# design1.net
KiCad netlist of a schematic drawn in Altium Designer
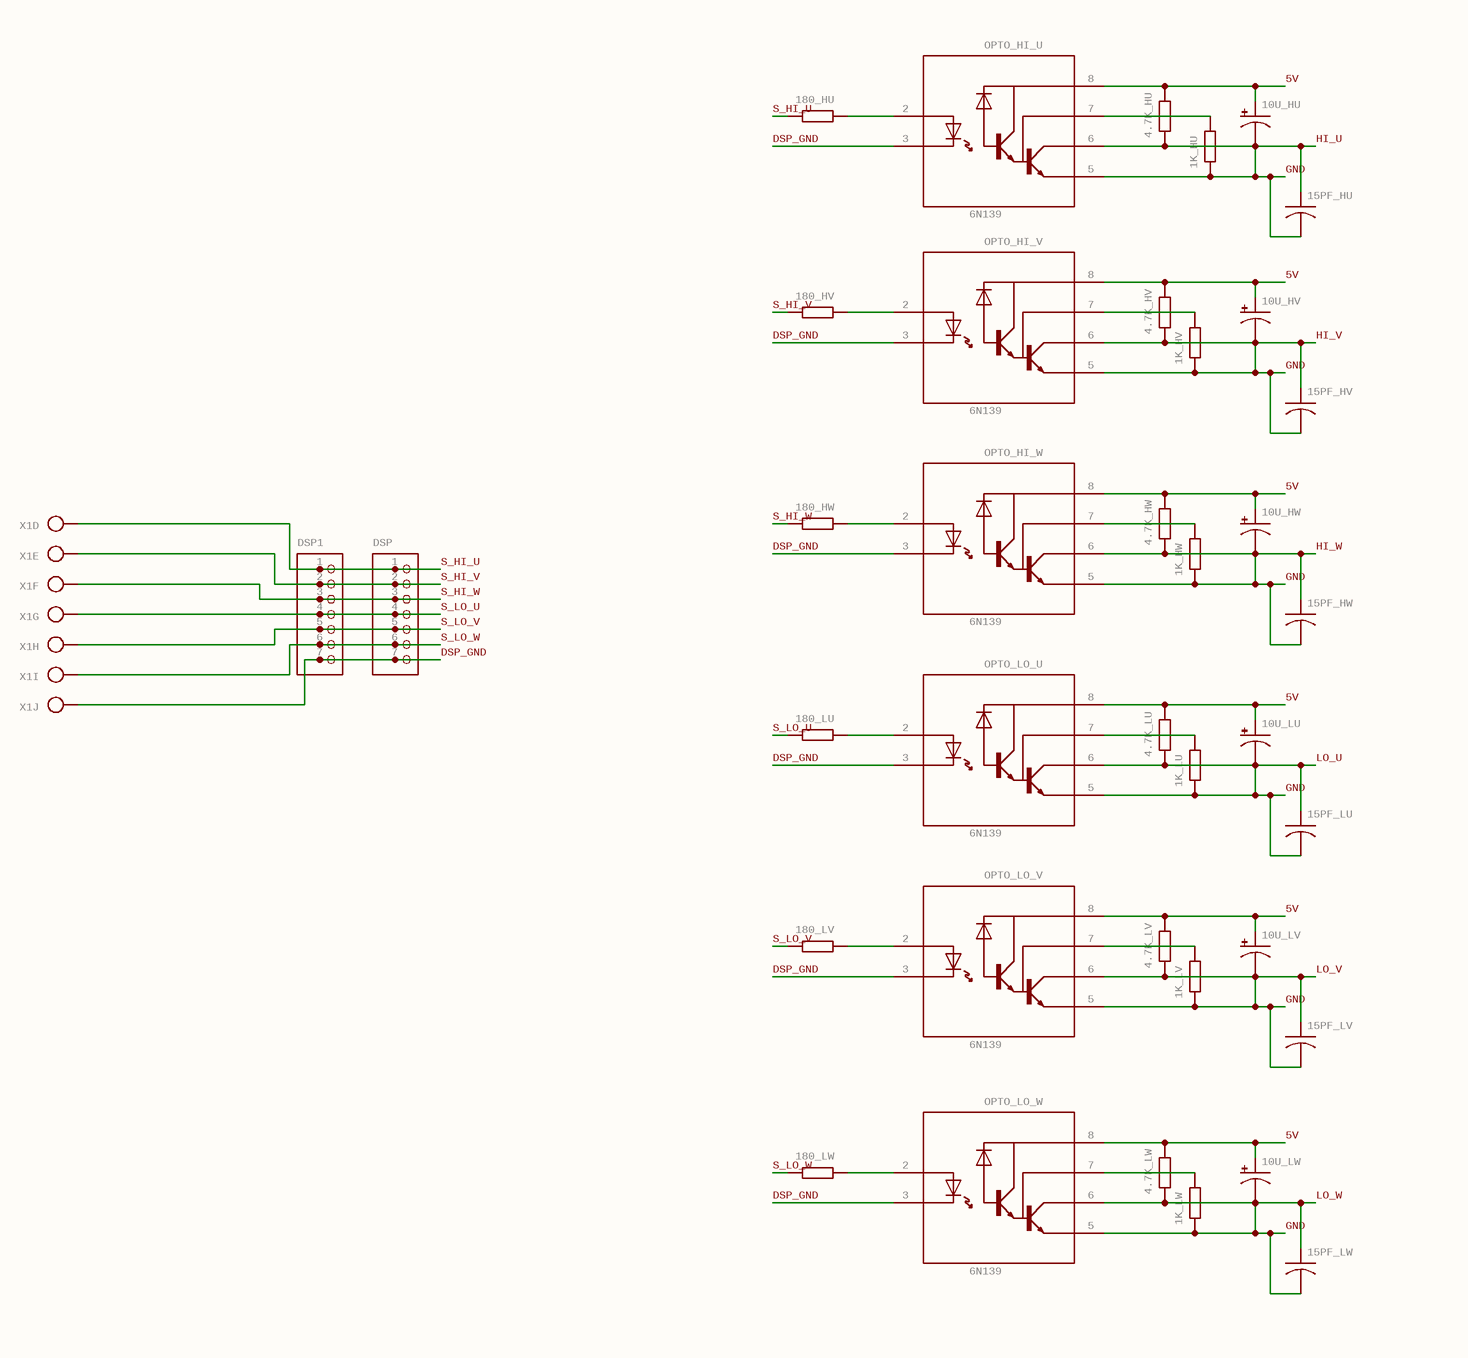
[diagram p0: design1.SchDoc, left]
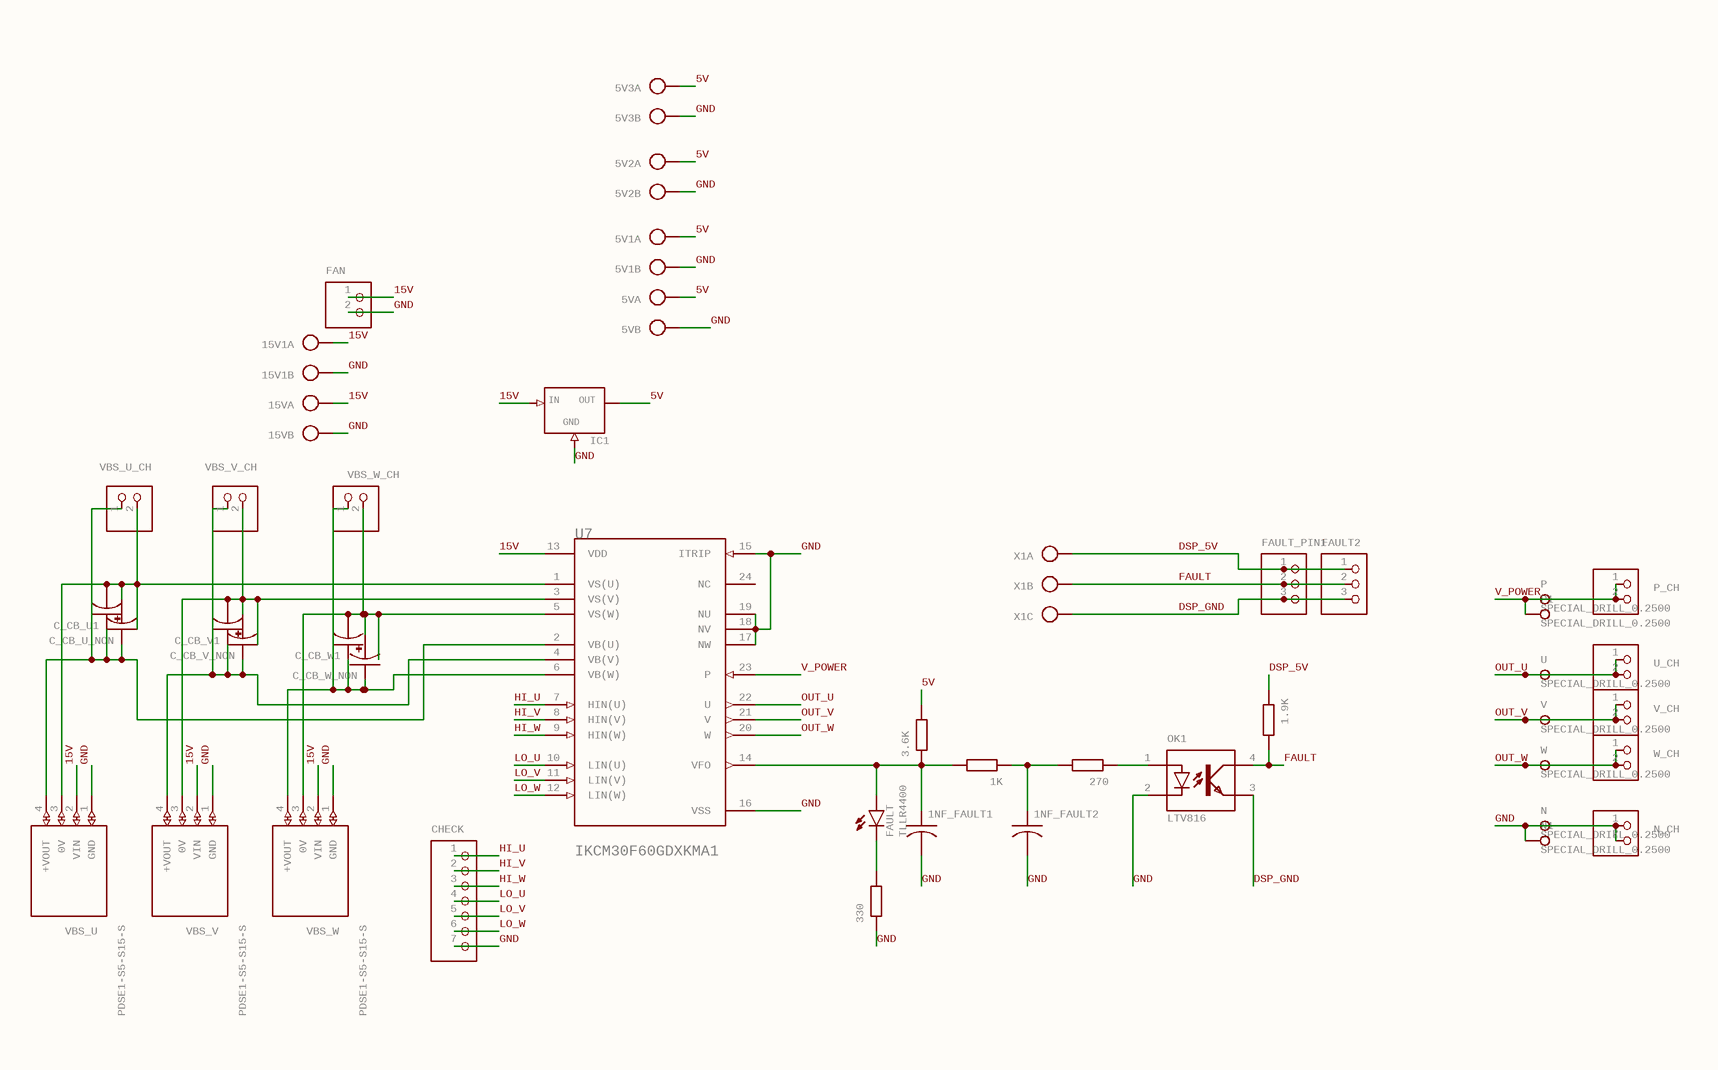
[diagram p1: design1.SchDoc, right]

(export (version "E")
  (design (tool "Eeschema 10.0.6"))
  (components
    (comp (ref "1.9K")
      (value "R-EU_0207/12")
      (footprint "0207/12")
      (description "RESISTOR, European symbol")
      (libsource (lib "rcl") (part "R-EU_0207/12"))
    )
    (comp (ref "1K")
      (value "R-EU_0207/12")
      (footprint "0207/12")
      (description "RESISTOR, European symbol")
      (libsource (lib "rcl") (part "R-EU_0207/12"))
    )
    (comp (ref "1K_HU")
      (value "R-EU_0207/12")
      (footprint "0207/12")
      (description "RESISTOR, European symbol")
      (libsource (lib "rcl") (part "R-EU_0207/12"))
    )
    (comp (ref "1K_HV")
      (value "R-EU_0207/12")
      (footprint "0207/12")
      (description "RESISTOR, European symbol")
      (libsource (lib "rcl") (part "R-EU_0207/12"))
    )
    (comp (ref "1K_HW")
      (value "R-EU_0207/12")
      (footprint "0207/12")
      (description "RESISTOR, European symbol")
      (libsource (lib "rcl") (part "R-EU_0207/12"))
    )
    (comp (ref "1K_LU")
      (value "R-EU_0207/12")
      (footprint "0207/12")
      (description "RESISTOR, European symbol")
      (libsource (lib "rcl") (part "R-EU_0207/12"))
    )
    (comp (ref "1K_LV")
      (value "R-EU_0207/12")
      (footprint "0207/12")
      (description "RESISTOR, European symbol")
      (libsource (lib "rcl") (part "R-EU_0207/12"))
    )
    (comp (ref "1K_LW")
      (value "R-EU_0207/12")
      (footprint "0207/12")
      (description "RESISTOR, European symbol")
      (libsource (lib "rcl") (part "R-EU_0207/12"))
    )
    (comp (ref "1NF_FAULT1")
      (value "C-US025-025X050")
      (footprint "C025-025X050")
      (description "CAPACITOR, American symbol")
      (libsource (lib "rcl") (part "C-US025-025X050"))
    )
    (comp (ref "1NF_FAULT2")
      (value "C-US025-025X050")
      (footprint "C025-025X050")
      (description "CAPACITOR, American symbol")
      (libsource (lib "rcl") (part "C-US025-025X050"))
    )
    (comp (ref "3.6K")
      (value "R-EU_0207/12")
      (footprint "0207/12")
      (description "RESISTOR, European symbol")
      (libsource (lib "rcl") (part "R-EU_0207/12"))
    )
    (comp (ref "4.7K_HU")
      (value "R-EU_0207/12")
      (footprint "0207/12")
      (description "RESISTOR, European symbol")
      (libsource (lib "rcl") (part "R-EU_0207/12"))
    )
    (comp (ref "4.7K_HV")
      (value "R-EU_0207/12")
      (footprint "0207/12")
      (description "RESISTOR, European symbol")
      (libsource (lib "rcl") (part "R-EU_0207/12"))
    )
    (comp (ref "4.7K_HW")
      (value "R-EU_0207/12")
      (footprint "0207/12")
      (description "RESISTOR, European symbol")
      (libsource (lib "rcl") (part "R-EU_0207/12"))
    )
    (comp (ref "4.7K_LU")
      (value "R-EU_0207/12")
      (footprint "0207/12")
      (description "RESISTOR, European symbol")
      (libsource (lib "rcl") (part "R-EU_0207/12"))
    )
    (comp (ref "4.7K_LV")
      (value "R-EU_0207/12")
      (footprint "0207/12")
      (description "RESISTOR, European symbol")
      (libsource (lib "rcl") (part "R-EU_0207/12"))
    )
    (comp (ref "4.7K_LW")
      (value "R-EU_0207/12")
      (footprint "0207/12")
      (description "RESISTOR, European symbol")
      (libsource (lib "rcl") (part "R-EU_0207/12"))
    )
    (comp (ref "5V")
      (value "AK500/2")
      (footprint "AK500/2")
      (description "CONNECTOR")
      (fields (field (name "MF") "MF") (field (name "MPN") "MPN") (field (name "LIBRARYNAME") "con-ptr500"))
      (libsource (lib "con-ptr500") (part "AK500/2"))
    )
    (comp (ref "5V1")
      (value "AK500/2")
      (footprint "AK500/2")
      (description "CONNECTOR")
      (fields (field (name "MF") "MF") (field (name "MPN") "MPN") (field (name "LIBRARYNAME") "con-ptr500"))
      (libsource (lib "con-ptr500") (part "AK500/2"))
    )
    (comp (ref "5V2")
      (value "AK500/2")
      (footprint "AK500/2")
      (description "CONNECTOR")
      (fields (field (name "MF") "MF") (field (name "MPN") "MPN") (field (name "LIBRARYNAME") "con-ptr500"))
      (libsource (lib "con-ptr500") (part "AK500/2"))
    )
    (comp (ref "5V3")
      (value "AK500/2")
      (footprint "AK500/2")
      (description "CONNECTOR")
      (fields (field (name "MF") "MF") (field (name "MPN") "MPN") (field (name "LIBRARYNAME") "con-ptr500"))
      (libsource (lib "con-ptr500") (part "AK500/2"))
    )
    (comp (ref "10U_HU")
      (value "CPOL-USE2-4")
      (footprint "E2-4")
      (description "POLARIZED CAPACITOR, American symbol")
      (libsource (lib "rcl") (part "CPOL-USE2-4"))
    )
    (comp (ref "10U_HV")
      (value "CPOL-USE2-4")
      (footprint "E2-4")
      (description "POLARIZED CAPACITOR, American symbol")
      (libsource (lib "rcl") (part "CPOL-USE2-4"))
    )
    (comp (ref "10U_HW")
      (value "CPOL-USE2-4")
      (footprint "E2-4")
      (description "POLARIZED CAPACITOR, American symbol")
      (libsource (lib "rcl") (part "CPOL-USE2-4"))
    )
    (comp (ref "10U_LU")
      (value "CPOL-USE2-4")
      (footprint "E2-4")
      (description "POLARIZED CAPACITOR, American symbol")
      (libsource (lib "rcl") (part "CPOL-USE2-4"))
    )
    (comp (ref "10U_LV")
      (value "CPOL-USE2-4")
      (footprint "E2-4")
      (description "POLARIZED CAPACITOR, American symbol")
      (libsource (lib "rcl") (part "CPOL-USE2-4"))
    )
    (comp (ref "10U_LW")
      (value "CPOL-USE2-4")
      (footprint "E2-4")
      (description "POLARIZED CAPACITOR, American symbol")
      (libsource (lib "rcl") (part "CPOL-USE2-4"))
    )
    (comp (ref "15PF_HU")
      (value "C-US025-025X050")
      (footprint "C025-025X050")
      (description "CAPACITOR, American symbol")
      (libsource (lib "rcl") (part "C-US025-025X050"))
    )
    (comp (ref "15PF_HV")
      (value "C-US025-025X050")
      (footprint "C025-025X050")
      (description "CAPACITOR, American symbol")
      (libsource (lib "rcl") (part "C-US025-025X050"))
    )
    (comp (ref "15PF_HW")
      (value "C-US025-025X050")
      (footprint "C025-025X050")
      (description "CAPACITOR, American symbol")
      (libsource (lib "rcl") (part "C-US025-025X050"))
    )
    (comp (ref "15PF_LU")
      (value "C-US025-025X050")
      (footprint "C025-025X050")
      (description "CAPACITOR, American symbol")
      (libsource (lib "rcl") (part "C-US025-025X050"))
    )
    (comp (ref "15PF_LV")
      (value "C-US025-025X050")
      (footprint "C025-025X050")
      (description "CAPACITOR, American symbol")
      (libsource (lib "rcl") (part "C-US025-025X050"))
    )
    (comp (ref "15PF_LW")
      (value "C-US025-025X050")
      (footprint "C025-025X050")
      (description "CAPACITOR, American symbol")
      (libsource (lib "rcl") (part "C-US025-025X050"))
    )
    (comp (ref "15V")
      (value "AK500/2")
      (footprint "AK500/2")
      (description "CONNECTOR")
      (fields (field (name "MF") "MF") (field (name "MPN") "MPN") (field (name "LIBRARYNAME") "con-ptr500"))
      (libsource (lib "con-ptr500") (part "AK500/2"))
    )
    (comp (ref "15V1")
      (value "AK500/2")
      (footprint "AK500/2")
      (description "CONNECTOR")
      (fields (field (name "MF") "MF") (field (name "MPN") "MPN") (field (name "LIBRARYNAME") "con-ptr500"))
      (libsource (lib "con-ptr500") (part "AK500/2"))
    )
    (comp (ref "180_HU")
      (value "R-EU_0207/12")
      (footprint "0207/12")
      (description "RESISTOR, European symbol")
      (libsource (lib "rcl") (part "R-EU_0207/12"))
    )
    (comp (ref "180_HV")
      (value "R-EU_0207/12")
      (footprint "0207/12")
      (description "RESISTOR, European symbol")
      (libsource (lib "rcl") (part "R-EU_0207/12"))
    )
    (comp (ref "180_HW")
      (value "R-EU_0207/12")
      (footprint "0207/12")
      (description "RESISTOR, European symbol")
      (libsource (lib "rcl") (part "R-EU_0207/12"))
    )
    (comp (ref "180_LU")
      (value "R-EU_0207/12")
      (footprint "0207/12")
      (description "RESISTOR, European symbol")
      (libsource (lib "rcl") (part "R-EU_0207/12"))
    )
    (comp (ref "180_LV")
      (value "R-EU_0207/12")
      (footprint "0207/12")
      (description "RESISTOR, European symbol")
      (libsource (lib "rcl") (part "R-EU_0207/12"))
    )
    (comp (ref "180_LW")
      (value "R-EU_0207/12")
      (footprint "0207/12")
      (description "RESISTOR, European symbol")
      (libsource (lib "rcl") (part "R-EU_0207/12"))
    )
    (comp (ref "270")
      (value "R-EU_0207/12")
      (footprint "0207/12")
      (description "RESISTOR, European symbol")
      (libsource (lib "rcl") (part "R-EU_0207/12"))
    )
    (comp (ref "330")
      (value "R-EU_0207/12")
      (footprint "0207/12")
      (description "RESISTOR, European symbol")
      (libsource (lib "rcl") (part "R-EU_0207/12"))
    )
    (comp (ref "CHECK")
      (value "PINHD-1X7")
      (footprint "1X07")
      (description "PIN HEADER")
      (fields (field (name "LIBRARYNAME") "pinhead"))
      (libsource (lib "pinhead") (part "PINHD-1X7"))
    )
    (comp (ref "C_CB_U1")
      (value "CPOL-USE2-4")
      (footprint "E2-4")
      (description "POLARIZED CAPACITOR, American symbol")
      (libsource (lib "") (part "CPOL-USE2-4_1"))
    )
    (comp (ref "C_CB_U_NON")
      (value "C-US025-025X050")
      (footprint "C025-025X050")
      (description "CAPACITOR, American symbol")
      (libsource (lib "rcl") (part "C-US025-025X050"))
    )
    (comp (ref "C_CB_V1")
      (value "CPOL-USE2-4")
      (footprint "E2-4")
      (description "POLARIZED CAPACITOR, American symbol")
      (libsource (lib "") (part "CPOL-USE2-4_1"))
    )
    (comp (ref "C_CB_V_NON")
      (value "C-US025-025X050")
      (footprint "C025-025X050")
      (description "CAPACITOR, American symbol")
      (libsource (lib "rcl") (part "C-US025-025X050"))
    )
    (comp (ref "C_CB_W1")
      (value "CPOL-USE2-4")
      (footprint "E2-4")
      (description "POLARIZED CAPACITOR, American symbol")
      (libsource (lib "") (part "CPOL-USE2-4_1"))
    )
    (comp (ref "C_CB_W_NON")
      (value "C-US025-025X050")
      (footprint "C025-025X050")
      (description "CAPACITOR, American symbol")
      (libsource (lib "rcl") (part "C-US025-025X050"))
    )
    (comp (ref "DSP")
      (value "PINHD-1X7/90")
      (footprint "1X07/90")
      (description "PIN HEADER")
      (fields (field (name "LIBRARYNAME") "pinhead"))
      (libsource (lib "pinhead") (part "PINHD-1X7/90"))
    )
    (comp (ref "DSP1")
      (value "PINHD-1X7")
      (footprint "1X07")
      (description "PIN HEADER")
      (fields (field (name "LIBRARYNAME") "pinhead"))
      (libsource (lib "pinhead") (part "PINHD-1X7"))
    )
    (comp (ref "FAN")
      (value "PINHD-1X2")
      (footprint "1X02")
      (description "PIN HEADER")
      (fields (field (name "LIBRARYNAME") "pinhead"))
      (libsource (lib "pinhead") (part "PINHD-1X2"))
    )
    (comp (ref "FAULT")
      (value "TLLR4400")
      (footprint "LED3MM")
      (description "Low Current (2mA) LED 3 mm Tinted Diffused Package color RED   Source:  Data sheet")
      (fields (field (name "MF") "VISHAY SEMICONDUCTOR"))
      (libsource (lib "led") (part "TLLR4400"))
    )
    (comp (ref "FAULT2")
      (value "PINHD-1X3/90")
      (footprint "1X03/90")
      (description "PIN HEADER")
      (fields (field (name "LIBRARYNAME") "pinhead"))
      (libsource (lib "pinhead") (part "PINHD-1X3/90"))
    )
    (comp (ref "FAULT_PIN1")
      (value "PINHD-1X3")
      (footprint "1X03")
      (description "PIN HEADER")
      (fields (field (name "LIBRARYNAME") "pinhead"))
      (libsource (lib "pinhead") (part "PINHD-1X3"))
    )
    (comp (ref "IC1")
      (value "78XXS")
      (footprint "78XXS")
      (description "VOLTAGE REGULATOR")
      (fields (field (name "GND") "GND") (field (name "IN") "IN") (field (name "OUT") "OUT"))
      (libsource (lib "v-reg") (part "78XXS"))
    )
    (comp (ref "N")
      (value "SPECIAL_DRILL_0.2500")
      (footprint "PAD_0.2500")
      (description "Special drills")
      (libsource (lib "special-drill") (part "SPECIAL_DRILL_0.2500"))
    )
    (comp (ref "N1")
      (value "SPECIAL_DRILL_0.2500")
      (footprint "PAD_0.2500")
      (description "Special drills")
      (libsource (lib "special-drill") (part "SPECIAL_DRILL_0.2500"))
    )
    (comp (ref "N_CH")
      (value "PINHD-1X2")
      (footprint "1X02")
      (description "PIN HEADER")
      (fields (field (name "LIBRARYNAME") "pinhead"))
      (libsource (lib "pinhead") (part "PINHD-1X2"))
    )
    (comp (ref "OK1")
      (value "LTV816")
      (footprint "DIL04")
      (description "OPTO COUPLER   Source: LITEON, LTV816.pdf")
      (fields (field (name "MF") "MF") (field (name "MPN") "MPN"))
      (libsource (lib "optocoupler") (part "LTV816"))
    )
    (comp (ref "OPTO_HI_U")
      (value "6N139")
      (footprint "DIP762W50P254L977H451Q8")
      (fields (field (name "MF") "Vishay Semiconductor"))
      (libsource (lib "6N139") (part "6N139"))
    )
    (comp (ref "OPTO_HI_V")
      (value "6N139")
      (footprint "DIP762W50P254L977H451Q8")
      (fields (field (name "MF") "Vishay Semiconductor"))
      (libsource (lib "6N139") (part "6N139"))
    )
    (comp (ref "OPTO_HI_W")
      (value "6N139")
      (footprint "DIP762W50P254L977H451Q8")
      (fields (field (name "MF") "Vishay Semiconductor"))
      (libsource (lib "6N139") (part "6N139"))
    )
    (comp (ref "OPTO_LO_U")
      (value "6N139")
      (footprint "DIP762W50P254L977H451Q8")
      (fields (field (name "MF") "Vishay Semiconductor"))
      (libsource (lib "6N139") (part "6N139"))
    )
    (comp (ref "OPTO_LO_V")
      (value "6N139")
      (footprint "DIP762W50P254L977H451Q8")
      (fields (field (name "MF") "Vishay Semiconductor"))
      (libsource (lib "6N139") (part "6N139"))
    )
    (comp (ref "OPTO_LO_W")
      (value "6N139")
      (footprint "DIP762W50P254L977H451Q8")
      (fields (field (name "MF") "Vishay Semiconductor"))
      (libsource (lib "6N139") (part "6N139"))
    )
    (comp (ref "P")
      (value "SPECIAL_DRILL_0.2500")
      (footprint "PAD_0.2500")
      (description "Special drills")
      (libsource (lib "special-drill") (part "SPECIAL_DRILL_0.2500"))
    )
    (comp (ref "P1")
      (value "SPECIAL_DRILL_0.2500")
      (footprint "PAD_0.2500")
      (description "Special drills")
      (libsource (lib "special-drill") (part "SPECIAL_DRILL_0.2500"))
    )
    (comp (ref "P_CH")
      (value "PINHD-1X2")
      (footprint "1X02")
      (description "PIN HEADER")
      (fields (field (name "LIBRARYNAME") "pinhead"))
      (libsource (lib "pinhead") (part "PINHD-1X2"))
    )
    (comp (ref "U")
      (value "SPECIAL_DRILL_0.2500")
      (footprint "PAD_0.2500")
      (description "Special drills")
      (libsource (lib "special-drill") (part "SPECIAL_DRILL_0.2500"))
    )
    (comp (ref "U7")
      (value "INFINEON_IKCM30F60GDXKMA1INFINEON_IKCM30F60GDXKMA1_0_0")
      (footprint "INFINEON_IKCM30F60GDXKMA1_0")
      (description "Trans IGBT Module N-CH 24-Pin MDIP")
      (fields
        (field (name "IKCM30F60GDXKMA1") "IKCM30F60GDXKMA1")
        (field (name "DIGIKEY_PART_NUMBER") "IKCM30F60GDXKMA1-ND")
        (field (name "MF") "Infineon")
      )
      (libsource (lib "Infineon - IKCM30F60GDXKMA1") (part "INFINEON_IKCM30F60GDXKMA1INFINEON_IKCM30F60GDXKMA1_0_0"))
    )
    (comp (ref "U_CH")
      (value "PINHD-1X2")
      (footprint "1X02")
      (description "PIN HEADER")
      (fields (field (name "LIBRARYNAME") "pinhead"))
      (libsource (lib "pinhead") (part "PINHD-1X2"))
    )
    (comp (ref "V")
      (value "SPECIAL_DRILL_0.2500")
      (footprint "PAD_0.2500")
      (description "Special drills")
      (libsource (lib "special-drill") (part "SPECIAL_DRILL_0.2500"))
    )
    (comp (ref "VBS_U")
      (value "PDSE1-S5-S15-S")
      (footprint "PDSE1S5S15S")
      (fields (field (name "UTMEL_PART_NUMBER") "UTMEL_PART_NUMBER"))
      (libsource (lib "PDSE1-S5-S15-S") (part "PDSE1-S5-S15-S"))
    )
    (comp (ref "VBS_U_CH")
      (value "PINHD-1X2")
      (footprint "1X02")
      (description "PIN HEADER")
      (fields (field (name "LIBRARYNAME") "pinhead"))
      (libsource (lib "pinhead") (part "PINHD-1X2"))
    )
    (comp (ref "VBS_V")
      (value "PDSE1-S5-S15-S")
      (footprint "PDSE1S5S15S")
      (fields (field (name "UTMEL_PART_NUMBER") "UTMEL_PART_NUMBER"))
      (libsource (lib "PDSE1-S5-S15-S") (part "PDSE1-S5-S15-S"))
    )
    (comp (ref "VBS_V_CH")
      (value "PINHD-1X2")
      (footprint "1X02")
      (description "PIN HEADER")
      (fields (field (name "LIBRARYNAME") "pinhead"))
      (libsource (lib "pinhead") (part "PINHD-1X2"))
    )
    (comp (ref "VBS_W")
      (value "PDSE1-S5-S15-S")
      (footprint "PDSE1S5S15S")
      (fields (field (name "UTMEL_PART_NUMBER") "UTMEL_PART_NUMBER"))
      (libsource (lib "PDSE1-S5-S15-S") (part "PDSE1-S5-S15-S"))
    )
    (comp (ref "VBS_W_CH")
      (value "PINHD-1X2")
      (footprint "1X02")
      (description "PIN HEADER")
      (fields (field (name "LIBRARYNAME") "pinhead"))
      (libsource (lib "pinhead") (part "PINHD-1X2"))
    )
    (comp (ref "V_CH")
      (value "PINHD-1X2")
      (footprint "1X02")
      (description "PIN HEADER")
      (fields (field (name "LIBRARYNAME") "pinhead"))
      (libsource (lib "pinhead") (part "PINHD-1X2"))
    )
    (comp (ref "W")
      (value "SPECIAL_DRILL_0.2500")
      (footprint "PAD_0.2500")
      (description "Special drills")
      (libsource (lib "special-drill") (part "SPECIAL_DRILL_0.2500"))
    )
    (comp (ref "W_CH")
      (value "PINHD-1X2")
      (footprint "1X02")
      (description "PIN HEADER")
      (fields (field (name "LIBRARYNAME") "pinhead"))
      (libsource (lib "pinhead") (part "PINHD-1X2"))
    )
    (comp (ref "X1")
      (value "AK500/10")
      (footprint "AK500/10")
      (description "CONNECTOR")
      (fields (field (name "MF") "MF") (field (name "MPN") "MPN") (field (name "LIBRARYNAME") "con-ptr500"))
      (libsource (lib "con-ptr500") (part "AK500/10"))
    )
  )
  (nets
    (net (code "1") (name "/5V") (class "Default")
      (node (ref "10U_HU") (pin "+") (pinfunction "+_+") (pintype "passive"))
      (node (ref "10U_HV") (pin "+") (pinfunction "+_+") (pintype "passive"))
      (node (ref "10U_HW") (pin "+") (pinfunction "+_+") (pintype "passive"))
      (node (ref "10U_LU") (pin "+") (pinfunction "+_+") (pintype "passive"))
      (node (ref "10U_LV") (pin "+") (pinfunction "+_+") (pintype "passive"))
      (node (ref "10U_LW") (pin "+") (pinfunction "+_+") (pintype "passive"))
      (node (ref "3.6K") (pin "2") (pinfunction "2_2") (pintype "passive"))
      (node (ref "4.7K_HU") (pin "2") (pinfunction "2_2") (pintype "passive"))
      (node (ref "4.7K_HV") (pin "2") (pinfunction "2_2") (pintype "passive"))
      (node (ref "4.7K_HW") (pin "2") (pinfunction "2_2") (pintype "passive"))
      (node (ref "4.7K_LU") (pin "2") (pinfunction "2_2") (pintype "passive"))
      (node (ref "4.7K_LV") (pin "2") (pinfunction "2_2") (pintype "passive"))
      (node (ref "4.7K_LW") (pin "2") (pinfunction "2_2") (pintype "passive"))
      (node (ref "5V") (pin "1") (pinfunction "KL_1") (pintype "passive"))
      (node (ref "5V1") (pin "1") (pinfunction "KL_1") (pintype "passive"))
      (node (ref "5V2") (pin "1") (pinfunction "KL_1") (pintype "passive"))
      (node (ref "5V3") (pin "1") (pinfunction "KL_1") (pintype "passive"))
      (node (ref "IC1") (pin "OUT") (pinfunction "OUT_OUT") (pintype "passive"))
      (node (ref "OPTO_HI_U") (pin "8") (pinfunction "VCC_8") (pintype "power_in"))
      (node (ref "OPTO_HI_V") (pin "8") (pinfunction "VCC_8") (pintype "power_in"))
      (node (ref "OPTO_HI_W") (pin "8") (pinfunction "VCC_8") (pintype "power_in"))
      (node (ref "OPTO_LO_U") (pin "8") (pinfunction "VCC_8") (pintype "power_in"))
      (node (ref "OPTO_LO_V") (pin "8") (pinfunction "VCC_8") (pintype "power_in"))
      (node (ref "OPTO_LO_W") (pin "8") (pinfunction "VCC_8") (pintype "power_in"))
    )
    (net (code "2") (name "/15V") (class "Default")
      (node (ref "15V") (pin "1") (pinfunction "KL_1") (pintype "passive"))
      (node (ref "15V1") (pin "1") (pinfunction "KL_1") (pintype "passive"))
      (node (ref "FAN") (pin "1") (pinfunction "1_1") (pintype "passive"))
      (node (ref "IC1") (pin "IN") (pinfunction "IN_IN") (pintype "input"))
      (node (ref "U7") (pin "13") (pinfunction "VDD_13") (pintype "power_in"))
      (node (ref "VBS_U") (pin "2") (pinfunction "VIN_2") (pintype "bidirectional"))
      (node (ref "VBS_V") (pin "2") (pinfunction "VIN_2") (pintype "bidirectional"))
      (node (ref "VBS_W") (pin "2") (pinfunction "VIN_2") (pintype "bidirectional"))
    )
    (net (code "3") (name "/DSP_5V") (class "Default")
      (node (ref "1.9K") (pin "1") (pinfunction "1_1") (pintype "passive"))
      (node (ref "FAULT2") (pin "1") (pinfunction "1_1") (pintype "passive"))
      (node (ref "FAULT_PIN1") (pin "1") (pinfunction "1_1") (pintype "passive"))
      (node (ref "X1") (pin "1") (pinfunction "KL_1") (pintype "passive"))
    )
    (net (code "4") (name "/DSP_GND") (class "Default")
      (node (ref "DSP") (pin "7") (pinfunction "7_7") (pintype "passive"))
      (node (ref "DSP1") (pin "7") (pinfunction "7_7") (pintype "passive"))
      (node (ref "FAULT2") (pin "3") (pinfunction "3_3") (pintype "passive"))
      (node (ref "FAULT_PIN1") (pin "3") (pinfunction "3_3") (pintype "passive"))
      (node (ref "OK1") (pin "3") (pinfunction "EMIT_3") (pintype "passive"))
      (node (ref "OPTO_HI_U") (pin "3") (pinfunction "C_3") (pintype "passive"))
      (node (ref "OPTO_HI_V") (pin "3") (pinfunction "C_3") (pintype "passive"))
      (node (ref "OPTO_HI_W") (pin "3") (pinfunction "C_3") (pintype "passive"))
      (node (ref "OPTO_LO_U") (pin "3") (pinfunction "C_3") (pintype "passive"))
      (node (ref "OPTO_LO_V") (pin "3") (pinfunction "C_3") (pintype "passive"))
      (node (ref "OPTO_LO_W") (pin "3") (pinfunction "C_3") (pintype "passive"))
      (node (ref "X1") (pin "10") (pinfunction "KL_10") (pintype "passive"))
      (node (ref "X1") (pin "3") (pinfunction "KL_3") (pintype "passive"))
    )
    (net (code "5") (name "/FAULT") (class "Default")
      (node (ref "1.9K") (pin "2") (pinfunction "2_2") (pintype "passive"))
      (node (ref "FAULT2") (pin "2") (pinfunction "2_2") (pintype "passive"))
      (node (ref "FAULT_PIN1") (pin "2") (pinfunction "2_2") (pintype "passive"))
      (node (ref "OK1") (pin "4") (pinfunction "COL_4") (pintype "passive"))
      (node (ref "X1") (pin "2") (pinfunction "KL_2") (pintype "passive"))
    )
    (net (code "6") (name "/GND") (class "Default")
      (node (ref "10U_HU") (pin "-") (pinfunction "-_-") (pintype "passive"))
      (node (ref "10U_HV") (pin "-") (pinfunction "-_-") (pintype "passive"))
      (node (ref "10U_HW") (pin "-") (pinfunction "-_-") (pintype "passive"))
      (node (ref "10U_LU") (pin "-") (pinfunction "-_-") (pintype "passive"))
      (node (ref "10U_LV") (pin "-") (pinfunction "-_-") (pintype "passive"))
      (node (ref "10U_LW") (pin "-") (pinfunction "-_-") (pintype "passive"))
      (node (ref "15PF_HU") (pin "1") (pinfunction "1_1") (pintype "passive"))
      (node (ref "15PF_HU") (pin "2") (pinfunction "2_2") (pintype "passive"))
      (node (ref "15PF_HV") (pin "1") (pinfunction "1_1") (pintype "passive"))
      (node (ref "15PF_HV") (pin "2") (pinfunction "2_2") (pintype "passive"))
      (node (ref "15PF_HW") (pin "1") (pinfunction "1_1") (pintype "passive"))
      (node (ref "15PF_HW") (pin "2") (pinfunction "2_2") (pintype "passive"))
      (node (ref "15PF_LU") (pin "1") (pinfunction "1_1") (pintype "passive"))
      (node (ref "15PF_LU") (pin "2") (pinfunction "2_2") (pintype "passive"))
      (node (ref "15PF_LV") (pin "1") (pinfunction "1_1") (pintype "passive"))
      (node (ref "15PF_LV") (pin "2") (pinfunction "2_2") (pintype "passive"))
      (node (ref "15PF_LW") (pin "1") (pinfunction "1_1") (pintype "passive"))
      (node (ref "15PF_LW") (pin "2") (pinfunction "2_2") (pintype "passive"))
      (node (ref "15V") (pin "2") (pinfunction "KL_2") (pintype "passive"))
      (node (ref "15V1") (pin "2") (pinfunction "KL_2") (pintype "passive"))
      (node (ref "1K_HU") (pin "1") (pinfunction "1_1") (pintype "passive"))
      (node (ref "1K_HV") (pin "1") (pinfunction "1_1") (pintype "passive"))
      (node (ref "1K_HW") (pin "1") (pinfunction "1_1") (pintype "passive"))
      (node (ref "1K_LU") (pin "1") (pinfunction "1_1") (pintype "passive"))
      (node (ref "1K_LV") (pin "1") (pinfunction "1_1") (pintype "passive"))
      (node (ref "1K_LW") (pin "1") (pinfunction "1_1") (pintype "passive"))
      (node (ref "1NF_FAULT1") (pin "2") (pinfunction "2_2") (pintype "passive"))
      (node (ref "1NF_FAULT2") (pin "2") (pinfunction "2_2") (pintype "passive"))
      (node (ref "330") (pin "1") (pinfunction "1_1") (pintype "passive"))
      (node (ref "4.7K_HU") (pin "1") (pinfunction "1_1") (pintype "passive"))
      (node (ref "4.7K_HV") (pin "1") (pinfunction "1_1") (pintype "passive"))
      (node (ref "4.7K_HW") (pin "1") (pinfunction "1_1") (pintype "passive"))
      (node (ref "4.7K_LU") (pin "1") (pinfunction "1_1") (pintype "passive"))
      (node (ref "4.7K_LV") (pin "1") (pinfunction "1_1") (pintype "passive"))
      (node (ref "4.7K_LW") (pin "1") (pinfunction "1_1") (pintype "passive"))
      (node (ref "5V") (pin "2") (pinfunction "KL_2") (pintype "passive"))
      (node (ref "5V1") (pin "2") (pinfunction "KL_2") (pintype "passive"))
      (node (ref "5V2") (pin "2") (pinfunction "KL_2") (pintype "passive"))
      (node (ref "5V3") (pin "2") (pinfunction "KL_2") (pintype "passive"))
      (node (ref "CHECK") (pin "1") (pinfunction "1_1") (pintype "passive"))
      (node (ref "CHECK") (pin "2") (pinfunction "2_2") (pintype "passive"))
      (node (ref "CHECK") (pin "3") (pinfunction "3_3") (pintype "passive"))
      (node (ref "CHECK") (pin "4") (pinfunction "4_4") (pintype "passive"))
      (node (ref "CHECK") (pin "5") (pinfunction "5_5") (pintype "passive"))
      (node (ref "CHECK") (pin "6") (pinfunction "6_6") (pintype "passive"))
      (node (ref "CHECK") (pin "7") (pinfunction "7_7") (pintype "passive"))
      (node (ref "FAN") (pin "2") (pinfunction "2_2") (pintype "passive"))
      (node (ref "IC1") (pin "GND") (pinfunction "GND_GND") (pintype "input"))
      (node (ref "N") (pin "1") (pinfunction "1_1") (pintype "passive"))
      (node (ref "N1") (pin "1") (pinfunction "1_1") (pintype "passive"))
      (node (ref "N_CH") (pin "1") (pinfunction "1_1") (pintype "passive"))
      (node (ref "N_CH") (pin "2") (pinfunction "2_2") (pintype "passive"))
      (node (ref "OK1") (pin "2") (pinfunction "C_2") (pintype "passive"))
      (node (ref "OPTO_HI_U") (pin "5") (pinfunction "GND_5") (pintype "power_in"))
      (node (ref "OPTO_HI_U") (pin "6") (pinfunction "VO_6") (pintype "passive"))
      (node (ref "OPTO_HI_V") (pin "5") (pinfunction "GND_5") (pintype "power_in"))
      (node (ref "OPTO_HI_V") (pin "6") (pinfunction "VO_6") (pintype "passive"))
      (node (ref "OPTO_HI_W") (pin "5") (pinfunction "GND_5") (pintype "power_in"))
      (node (ref "OPTO_HI_W") (pin "6") (pinfunction "VO_6") (pintype "passive"))
      (node (ref "OPTO_LO_U") (pin "5") (pinfunction "GND_5") (pintype "power_in"))
      (node (ref "OPTO_LO_U") (pin "6") (pinfunction "VO_6") (pintype "passive"))
      (node (ref "OPTO_LO_V") (pin "5") (pinfunction "GND_5") (pintype "power_in"))
      (node (ref "OPTO_LO_V") (pin "6") (pinfunction "VO_6") (pintype "passive"))
      (node (ref "OPTO_LO_W") (pin "5") (pinfunction "GND_5") (pintype "power_in"))
      (node (ref "OPTO_LO_W") (pin "6") (pinfunction "VO_6") (pintype "passive"))
      (node (ref "U7") (pin "10") (pinfunction "LIN(U)_10") (pintype "input"))
      (node (ref "U7") (pin "11") (pinfunction "LIN(V)_11") (pintype "input"))
      (node (ref "U7") (pin "12") (pinfunction "LIN(W)_12") (pintype "input"))
      (node (ref "U7") (pin "15") (pinfunction "ITRIP_15") (pintype "input"))
      (node (ref "U7") (pin "16") (pinfunction "VSS_16") (pintype "power_in"))
      (node (ref "U7") (pin "17") (pinfunction "NW_17") (pintype "passive"))
      (node (ref "U7") (pin "18") (pinfunction "NV_18") (pintype "passive"))
      (node (ref "U7") (pin "19") (pinfunction "NU_19") (pintype "passive"))
      (node (ref "U7") (pin "7") (pinfunction "HIN(U)_7") (pintype "input"))
      (node (ref "U7") (pin "8") (pinfunction "HIN(V)_8") (pintype "input"))
      (node (ref "U7") (pin "9") (pinfunction "HIN(W)_9") (pintype "input"))
      (node (ref "VBS_U") (pin "1") (pinfunction "GND_1") (pintype "bidirectional"))
      (node (ref "VBS_V") (pin "1") (pinfunction "GND_1") (pintype "bidirectional"))
      (node (ref "VBS_W") (pin "1") (pinfunction "GND_1") (pintype "bidirectional"))
    )
    (net (code "7") (name "/OUT_U") (class "Default")
      (node (ref "U") (pin "1") (pinfunction "1_1") (pintype "passive"))
      (node (ref "U7") (pin "22") (pinfunction "U_22") (pintype "output"))
      (node (ref "U_CH") (pin "1") (pinfunction "1_1") (pintype "passive"))
      (node (ref "U_CH") (pin "2") (pinfunction "2_2") (pintype "passive"))
    )
    (net (code "8") (name "/OUT_V") (class "Default")
      (node (ref "U7") (pin "21") (pinfunction "V_21") (pintype "output"))
      (node (ref "V") (pin "1") (pinfunction "1_1") (pintype "passive"))
      (node (ref "V_CH") (pin "1") (pinfunction "1_1") (pintype "passive"))
      (node (ref "V_CH") (pin "2") (pinfunction "2_2") (pintype "passive"))
    )
    (net (code "9") (name "/OUT_W") (class "Default")
      (node (ref "U7") (pin "20") (pinfunction "W_20") (pintype "output"))
      (node (ref "W") (pin "1") (pinfunction "1_1") (pintype "passive"))
      (node (ref "W_CH") (pin "1") (pinfunction "1_1") (pintype "passive"))
      (node (ref "W_CH") (pin "2") (pinfunction "2_2") (pintype "passive"))
    )
    (net (code "10") (name "/S_HI_U") (class "Default")
      (node (ref "180_HU") (pin "1") (pinfunction "1_1") (pintype "passive"))
      (node (ref "DSP") (pin "1") (pinfunction "1_1") (pintype "passive"))
      (node (ref "DSP1") (pin "1") (pinfunction "1_1") (pintype "passive"))
      (node (ref "X1") (pin "4") (pinfunction "KL_4") (pintype "passive"))
    )
    (net (code "11") (name "/S_HI_V") (class "Default")
      (node (ref "180_HV") (pin "1") (pinfunction "1_1") (pintype "passive"))
      (node (ref "DSP") (pin "2") (pinfunction "2_2") (pintype "passive"))
      (node (ref "DSP1") (pin "2") (pinfunction "2_2") (pintype "passive"))
      (node (ref "X1") (pin "5") (pinfunction "KL_5") (pintype "passive"))
    )
    (net (code "12") (name "/S_HI_W") (class "Default")
      (node (ref "180_HW") (pin "1") (pinfunction "1_1") (pintype "passive"))
      (node (ref "DSP") (pin "3") (pinfunction "3_3") (pintype "passive"))
      (node (ref "DSP1") (pin "3") (pinfunction "3_3") (pintype "passive"))
      (node (ref "X1") (pin "6") (pinfunction "KL_6") (pintype "passive"))
    )
    (net (code "13") (name "/S_LO_U") (class "Default")
      (node (ref "180_LU") (pin "1") (pinfunction "1_1") (pintype "passive"))
      (node (ref "DSP") (pin "4") (pinfunction "4_4") (pintype "passive"))
      (node (ref "DSP1") (pin "4") (pinfunction "4_4") (pintype "passive"))
      (node (ref "X1") (pin "7") (pinfunction "KL_7") (pintype "passive"))
    )
    (net (code "14") (name "/S_LO_V") (class "Default")
      (node (ref "180_LV") (pin "1") (pinfunction "1_1") (pintype "passive"))
      (node (ref "DSP") (pin "5") (pinfunction "5_5") (pintype "passive"))
      (node (ref "DSP1") (pin "5") (pinfunction "5_5") (pintype "passive"))
      (node (ref "X1") (pin "8") (pinfunction "KL_8") (pintype "passive"))
    )
    (net (code "15") (name "/S_LO_W") (class "Default")
      (node (ref "180_LW") (pin "1") (pinfunction "1_1") (pintype "passive"))
      (node (ref "DSP") (pin "6") (pinfunction "6_6") (pintype "passive"))
      (node (ref "DSP1") (pin "6") (pinfunction "6_6") (pintype "passive"))
      (node (ref "X1") (pin "9") (pinfunction "KL_9") (pintype "passive"))
    )
    (net (code "16") (name "/V_POWER") (class "Default")
      (node (ref "P") (pin "1") (pinfunction "1_1") (pintype "passive"))
      (node (ref "P1") (pin "1") (pinfunction "1_1") (pintype "passive"))
      (node (ref "P_CH") (pin "1") (pinfunction "1_1") (pintype "passive"))
      (node (ref "P_CH") (pin "2") (pinfunction "2_2") (pintype "passive"))
      (node (ref "U7") (pin "23") (pinfunction "P_23") (pintype "input"))
    )
    (net (code "17") (name "Net-(1K-Pad1)") (class "Default")
      (node (ref "1K") (pin "1") (pinfunction "1_1") (pintype "passive"))
      (node (ref "1NF_FAULT2") (pin "1") (pinfunction "1_1") (pintype "passive"))
      (node (ref "270") (pin "2") (pinfunction "2_2") (pintype "passive"))
    )
    (net (code "18") (name "Net-(FAULT-C)") (class "Default")
      (node (ref "330") (pin "2") (pinfunction "2_2") (pintype "passive"))
      (node (ref "FAULT") (pin "K") (pinfunction "C_K") (pintype "passive"))
    )
    (net (code "19") (name "Net-(OK1-A)") (class "Default")
      (node (ref "270") (pin "1") (pinfunction "1_1") (pintype "passive"))
      (node (ref "OK1") (pin "1") (pinfunction "A_1") (pintype "passive"))
    )
    (net (code "20") (name "Net-(OPTO_HI_U-A)") (class "Default")
      (node (ref "180_HU") (pin "2") (pinfunction "2_2") (pintype "passive"))
      (node (ref "OPTO_HI_U") (pin "2") (pinfunction "A_2") (pintype "passive"))
    )
    (net (code "21") (name "Net-(OPTO_HI_U-VB)") (class "Default")
      (node (ref "1K_HU") (pin "2") (pinfunction "2_2") (pintype "passive"))
      (node (ref "OPTO_HI_U") (pin "7") (pinfunction "VB_7") (pintype "passive"))
    )
    (net (code "22") (name "Net-(OPTO_HI_V-A)") (class "Default")
      (node (ref "180_HV") (pin "2") (pinfunction "2_2") (pintype "passive"))
      (node (ref "OPTO_HI_V") (pin "2") (pinfunction "A_2") (pintype "passive"))
    )
    (net (code "23") (name "Net-(OPTO_HI_V-VB)") (class "Default")
      (node (ref "1K_HV") (pin "2") (pinfunction "2_2") (pintype "passive"))
      (node (ref "OPTO_HI_V") (pin "7") (pinfunction "VB_7") (pintype "passive"))
    )
    (net (code "24") (name "Net-(OPTO_HI_W-A)") (class "Default")
      (node (ref "180_HW") (pin "2") (pinfunction "2_2") (pintype "passive"))
      (node (ref "OPTO_HI_W") (pin "2") (pinfunction "A_2") (pintype "passive"))
    )
    (net (code "25") (name "Net-(OPTO_HI_W-VB)") (class "Default")
      (node (ref "1K_HW") (pin "2") (pinfunction "2_2") (pintype "passive"))
      (node (ref "OPTO_HI_W") (pin "7") (pinfunction "VB_7") (pintype "passive"))
    )
    (net (code "26") (name "Net-(OPTO_LO_U-A)") (class "Default")
      (node (ref "180_LU") (pin "2") (pinfunction "2_2") (pintype "passive"))
      (node (ref "OPTO_LO_U") (pin "2") (pinfunction "A_2") (pintype "passive"))
    )
    (net (code "27") (name "Net-(OPTO_LO_U-VB)") (class "Default")
      (node (ref "1K_LU") (pin "2") (pinfunction "2_2") (pintype "passive"))
      (node (ref "OPTO_LO_U") (pin "7") (pinfunction "VB_7") (pintype "passive"))
    )
    (net (code "28") (name "Net-(OPTO_LO_V-A)") (class "Default")
      (node (ref "180_LV") (pin "2") (pinfunction "2_2") (pintype "passive"))
      (node (ref "OPTO_LO_V") (pin "2") (pinfunction "A_2") (pintype "passive"))
    )
    (net (code "29") (name "Net-(OPTO_LO_V-VB)") (class "Default")
      (node (ref "1K_LV") (pin "2") (pinfunction "2_2") (pintype "passive"))
      (node (ref "OPTO_LO_V") (pin "7") (pinfunction "VB_7") (pintype "passive"))
    )
    (net (code "30") (name "Net-(OPTO_LO_W-A)") (class "Default")
      (node (ref "180_LW") (pin "2") (pinfunction "2_2") (pintype "passive"))
      (node (ref "OPTO_LO_W") (pin "2") (pinfunction "A_2") (pintype "passive"))
    )
    (net (code "31") (name "Net-(OPTO_LO_W-VB)") (class "Default")
      (node (ref "1K_LW") (pin "2") (pinfunction "2_2") (pintype "passive"))
      (node (ref "OPTO_LO_W") (pin "7") (pinfunction "VB_7") (pintype "passive"))
    )
    (net (code "32") (name "Net-(U7-VB(U))") (class "Default")
      (node (ref "C_CB_U1") (pin "+") (pinfunction "+_+") (pintype "passive"))
      (node (ref "C_CB_U_NON") (pin "1") (pinfunction "1_1") (pintype "passive"))
      (node (ref "U7") (pin "2") (pinfunction "VB(U)_2") (pintype "power_in"))
      (node (ref "VBS_U") (pin "4") (pinfunction "+VOUT_4") (pintype "bidirectional"))
      (node (ref "VBS_U_CH") (pin "1") (pinfunction "1_1") (pintype "passive"))
    )
    (net (code "33") (name "Net-(U7-VB(V))") (class "Default")
      (node (ref "C_CB_V1") (pin "+") (pinfunction "+_+") (pintype "passive"))
      (node (ref "C_CB_V_NON") (pin "1") (pinfunction "1_1") (pintype "passive"))
      (node (ref "U7") (pin "4") (pinfunction "VB(V)_4") (pintype "power_in"))
      (node (ref "VBS_V") (pin "4") (pinfunction "+VOUT_4") (pintype "bidirectional"))
      (node (ref "VBS_V_CH") (pin "1") (pinfunction "1_1") (pintype "passive"))
    )
    (net (code "34") (name "Net-(U7-VB(W))") (class "Default")
      (node (ref "C_CB_W1") (pin "+") (pinfunction "+_+") (pintype "passive"))
      (node (ref "C_CB_W_NON") (pin "1") (pinfunction "1_1") (pintype "passive"))
      (node (ref "U7") (pin "6") (pinfunction "VB(W)_6") (pintype "power_in"))
      (node (ref "VBS_W") (pin "4") (pinfunction "+VOUT_4") (pintype "bidirectional"))
      (node (ref "VBS_W_CH") (pin "1") (pinfunction "1_1") (pintype "passive"))
    )
    (net (code "35") (name "Net-(U7-VFO)") (class "Default")
      (node (ref "1K") (pin "2") (pinfunction "2_2") (pintype "passive"))
      (node (ref "1NF_FAULT1") (pin "1") (pinfunction "1_1") (pintype "passive"))
      (node (ref "3.6K") (pin "1") (pinfunction "1_1") (pintype "passive"))
      (node (ref "FAULT") (pin "A") (pinfunction "A_A") (pintype "passive"))
      (node (ref "U7") (pin "14") (pinfunction "VFO_14") (pintype "output"))
    )
    (net (code "36") (name "Net-(U7-VS(U))") (class "Default")
      (node (ref "C_CB_U1") (pin "-") (pinfunction "-_-") (pintype "passive"))
      (node (ref "C_CB_U_NON") (pin "2") (pinfunction "2_2") (pintype "passive"))
      (node (ref "U7") (pin "1") (pinfunction "VS(U)_1") (pintype "power_in"))
      (node (ref "VBS_U") (pin "3") (pinfunction "0V_3") (pintype "bidirectional"))
      (node (ref "VBS_U_CH") (pin "2") (pinfunction "2_2") (pintype "passive"))
    )
    (net (code "37") (name "Net-(U7-VS(V))") (class "Default")
      (node (ref "C_CB_V1") (pin "-") (pinfunction "-_-") (pintype "passive"))
      (node (ref "C_CB_V_NON") (pin "2") (pinfunction "2_2") (pintype "passive"))
      (node (ref "U7") (pin "3") (pinfunction "VS(V)_3") (pintype "power_in"))
      (node (ref "VBS_V") (pin "3") (pinfunction "0V_3") (pintype "bidirectional"))
      (node (ref "VBS_V_CH") (pin "2") (pinfunction "2_2") (pintype "passive"))
    )
    (net (code "38") (name "Net-(U7-VS(W))") (class "Default")
      (node (ref "C_CB_W1") (pin "-") (pinfunction "-_-") (pintype "passive"))
      (node (ref "C_CB_W_NON") (pin "2") (pinfunction "2_2") (pintype "passive"))
      (node (ref "U7") (pin "5") (pinfunction "VS(W)_5") (pintype "power_in"))
      (node (ref "VBS_W") (pin "3") (pinfunction "0V_3") (pintype "bidirectional"))
      (node (ref "VBS_W_CH") (pin "2") (pinfunction "2_2") (pintype "passive"))
    )
    (net (code "39") (name "unconnected-(U7-NC-Pad24)") (class "Default")
      (node (ref "U7") (pin "24") (pinfunction "NC_24") (pintype "passive"))
    )
  )
)
